# task5.net
KiCad netlist of a schematic drawn in Altium Designer
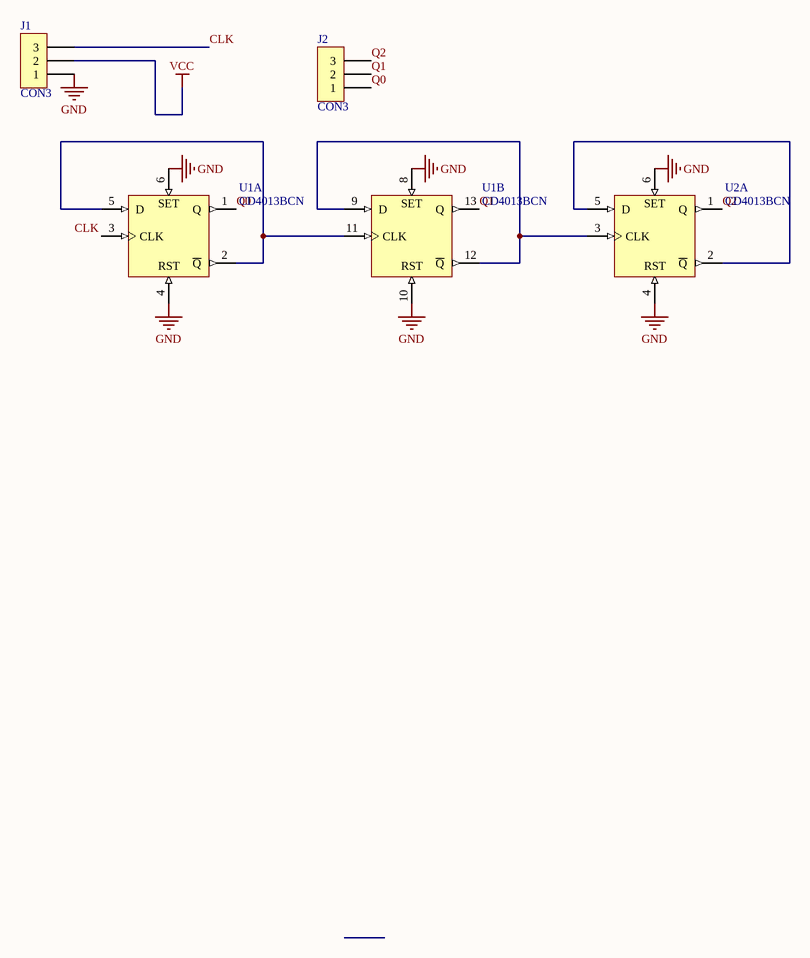
[diagram p0: task5.SchDoc]

(export (version "E")
  (design (tool "Eeschema 10.0.6"))
  (components
    (comp (ref "J1") (value "CON3") (footprint "SIP3") (libsource (lib "LIBEBAL") (part "CON3")))
    (comp (ref "J2") (value "CON3") (footprint "SIP3") (libsource (lib "LIBEBAL") (part "CON3")))
    (comp (ref "U1")
      (value "CD4013BCN")
      (footprint "N14A")
      (description "Dual D-Type Flip-Flop")
      (fields (field (name "PUBLISHER") "Altium Limited"))
      (libsource (lib "FSC Logic Flip-Flop") (part "CD4013BCN"))
    )
    (comp (ref "U2")
      (value "CD4013BCN")
      (footprint "N14A")
      (description "Dual D-Type Flip-Flop")
      (fields (field (name "PUBLISHER") "Altium Limited"))
      (libsource (lib "FSC Logic Flip-Flop") (part "CD4013BCN"))
    )
  )
  (nets
    (net (code "1") (name "/CLK") (class "Default")
      (node (ref "J1") (pin "3") (pinfunction "3_3") (pintype "passive"))
    )
    (net (code "2") (name "/Q0") (class "Default")
      (node (ref "J2") (pin "1") (pinfunction "1_1") (pintype "passive"))
      (node (ref "U1") (pin "1") (pinfunction "Q_1") (pintype "output"))
    )
    (net (code "3") (name "/Q1") (class "Default")
      (node (ref "J2") (pin "2") (pinfunction "2_2") (pintype "passive"))
      (node (ref "U1") (pin "13") (pinfunction "Q_13") (pintype "output"))
    )
    (net (code "4") (name "/Q2") (class "Default")
      (node (ref "J2") (pin "3") (pinfunction "3_3") (pintype "passive"))
      (node (ref "U2") (pin "1") (pinfunction "Q_1") (pintype "output"))
    )
    (net (code "5") (name "GND") (class "Default")
      (node (ref "J1") (pin "1") (pinfunction "1_1") (pintype "passive"))
      (node (ref "U1") (pin "10") (pinfunction "RST_10") (pintype "input"))
      (node (ref "U1") (pin "4") (pinfunction "RST_4") (pintype "input"))
      (node (ref "U1") (pin "6") (pinfunction "S_6") (pintype "input"))
      (node (ref "U1") (pin "7") (pinfunction "GND_7") (pintype "power_in"))
      (node (ref "U1") (pin "8") (pinfunction "S_8") (pintype "input"))
      (node (ref "U2") (pin "4") (pinfunction "RST_4") (pintype "input"))
      (node (ref "U2") (pin "6") (pinfunction "S_6") (pintype "input"))
      (node (ref "U2") (pin "7") (pinfunction "GND_7") (pintype "power_in"))
    )
    (net (code "6") (name "Net-(U1A-D)") (class "Default")
      (node (ref "U1") (pin "11") (pinfunction "CLK_11") (pintype "input"))
      (node (ref "U1") (pin "2") (pinfunction "~{Q}_2") (pintype "output"))
      (node (ref "U1") (pin "5") (pinfunction "D_5") (pintype "input"))
    )
    (net (code "7") (name "Net-(U1B-D)") (class "Default")
      (node (ref "U1") (pin "12") (pinfunction "~{Q}_12") (pintype "output"))
      (node (ref "U1") (pin "9") (pinfunction "D_9") (pintype "input"))
      (node (ref "U2") (pin "3") (pinfunction "CLK_3") (pintype "input"))
    )
    (net (code "8") (name "Net-(U2A-D)") (class "Default")
      (node (ref "U2") (pin "2") (pinfunction "~{Q}_2") (pintype "output"))
      (node (ref "U2") (pin "5") (pinfunction "D_5") (pintype "input"))
    )
    (net (code "9") (name "VCC") (class "Default")
      (node (ref "J1") (pin "2") (pinfunction "2_2") (pintype "passive"))
    )
    (net (code "10") (name "VDD") (class "Default")
      (node (ref "U1") (pin "14") (pinfunction "VDD_14") (pintype "power_in"))
      (node (ref "U2") (pin "14") (pinfunction "VDD_14") (pintype "power_in"))
    )
    (net (code "11") (name "unconnected-(U1A-CLK-Pad3)") (class "Default")
      (node (ref "U1") (pin "3") (pinfunction "CLK_3") (pintype "input"))
    )
  )
)
